# SCH_Research-Project_2024-03-07.net
KiCad netlist of a schematic drawn in EasyEDA
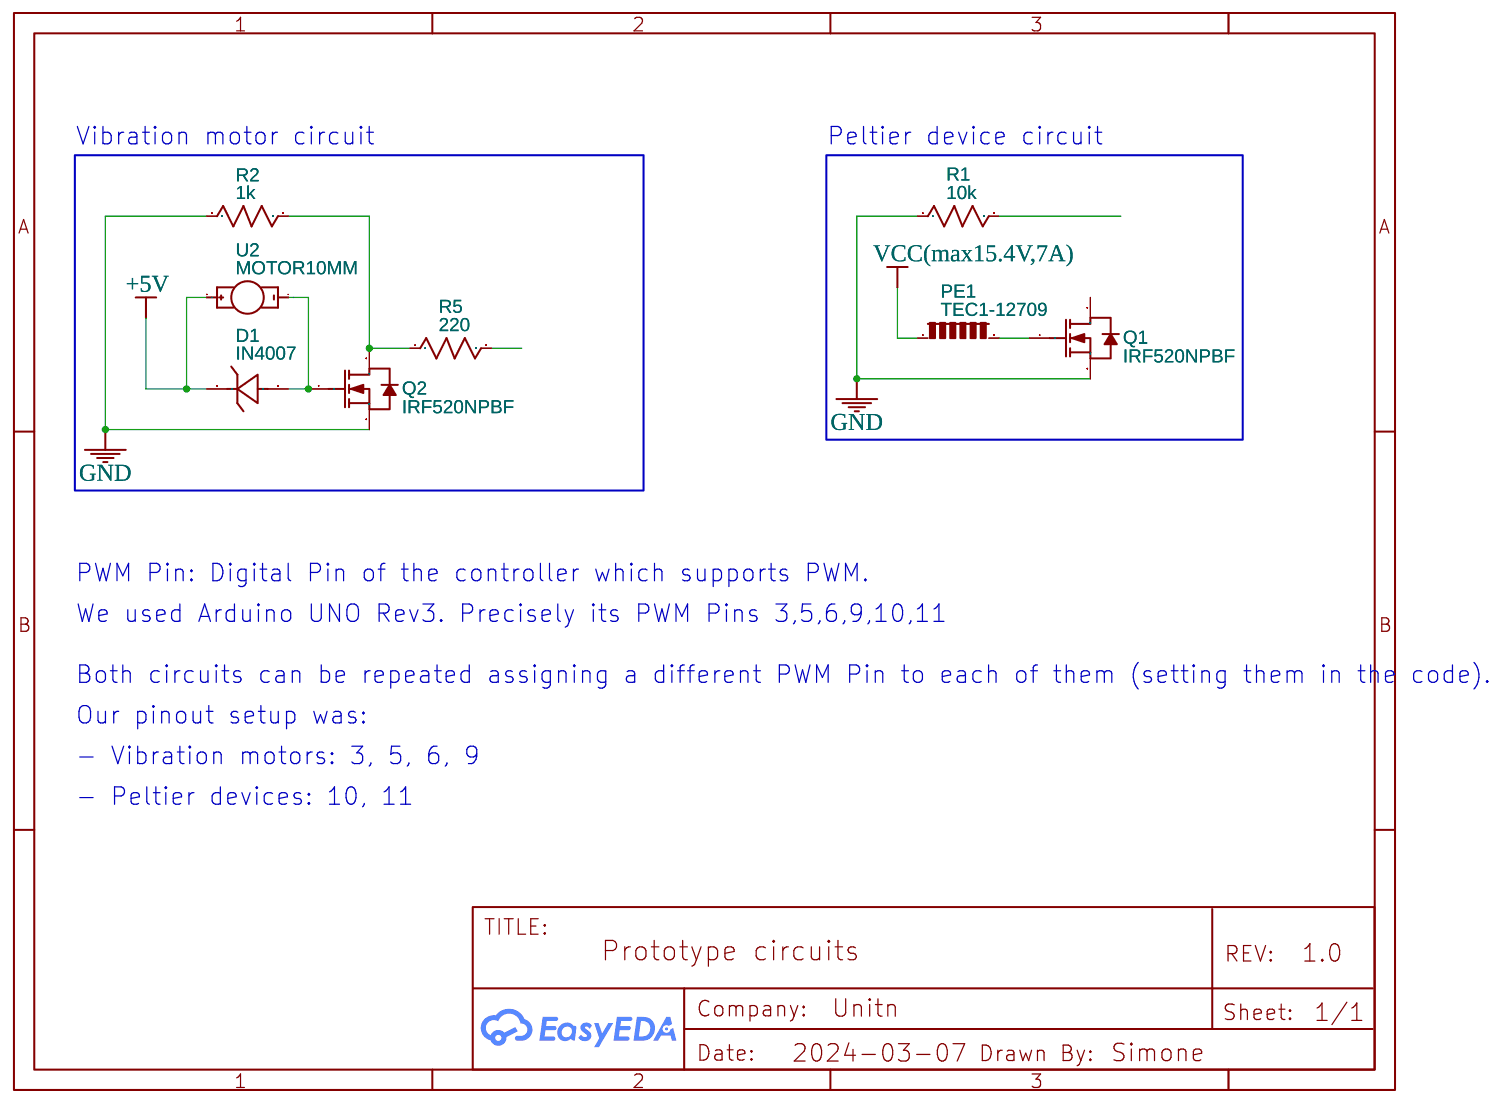
[diagram p0: schematic sheet]

(export (version "E")
  (design (tool "Eeschema 10.0.6"))
  (components
    (comp (ref "D1") (value "IN4007") (libsource (lib "") (part "IN4007")))
    (comp (ref "PE1") (value "TEC1-12709") (libsource (lib "") (part "Peltier_Element")))
    (comp (ref "Q1")
      (value "IRF520NPBF")
      (fields (field (name "Manufacturer") "Infineon(英飞凌)"))
      (libsource (lib "") (part "IRF520NPBF"))
    )
    (comp (ref "Q2")
      (value "IRF520NPBF")
      (fields (field (name "Manufacturer") "Infineon(英飞凌)"))
      (libsource (lib "") (part "IRF520NPBF"))
    )
    (comp (ref "R1") (value "10k") (libsource (lib "") (part "R_0603_US")))
    (comp (ref "R2") (value "1k") (libsource (lib "") (part "R_0603_US")))
    (comp (ref "R5") (value "220") (libsource (lib "") (part "R_0603_US")))
    (comp (ref "U2") (value "MOTOR10MM") (libsource (lib "") (part "MOTOR10MM")))
  )
  (nets
    (net (code "1") (name "+5V") (class "Default")
      (node (ref "D1") (pin "1") (pinfunction "C_1") (pintype "unspecified"))
      (node (ref "U2") (pin "+") (pinfunction "+_+") (pintype "unspecified"))
    )
    (net (code "2") (name "GND") (class "Default")
      (node (ref "Q1") (pin "3") (pinfunction "S_3") (pintype "unspecified"))
      (node (ref "Q2") (pin "3") (pinfunction "S_3") (pintype "unspecified"))
      (node (ref "R1") (pin "1") (pinfunction "1_1") (pintype "unspecified"))
      (node (ref "R2") (pin "1") (pinfunction "1_1") (pintype "unspecified"))
    )
    (net (code "3") (name "Net-(D1-A)") (class "Default")
      (node (ref "D1") (pin "2") (pinfunction "A_2") (pintype "unspecified"))
      (node (ref "Q2") (pin "1") (pinfunction "G_1") (pintype "unspecified"))
      (node (ref "U2") (pin "-") (pinfunction "-_-") (pintype "unspecified"))
    )
    (net (code "4") (name "Net-(Q1-G)") (class "Default")
      (node (ref "PE1") (pin "2") (pintype "unspecified"))
      (node (ref "Q1") (pin "1") (pinfunction "G_1") (pintype "unspecified"))
    )
    (net (code "5") (name "Net-(Q2-D)") (class "Default")
      (node (ref "Q2") (pin "2") (pinfunction "D_2") (pintype "unspecified"))
      (node (ref "R2") (pin "2") (pinfunction "2_2") (pintype "unspecified"))
      (node (ref "R5") (pin "1") (pinfunction "1_1") (pintype "unspecified"))
    )
    (net (code "6") (name "VCC(max15.4V,7A)") (class "Default")
      (node (ref "PE1") (pin "1") (pintype "unspecified"))
    )
    (net (code "7") (name "unconnected-(Q1-D-Pad2)") (class "Default")
      (node (ref "Q1") (pin "2") (pinfunction "D_2") (pintype "unspecified"))
    )
    (net (code "8") (name "unconnected-(R1-Pad2)") (class "Default")
      (node (ref "R1") (pin "2") (pinfunction "2_2") (pintype "unspecified"))
    )
    (net (code "9") (name "unconnected-(R5-Pad2)") (class "Default")
      (node (ref "R5") (pin "2") (pinfunction "2_2") (pintype "unspecified"))
    )
  )
)
